# EEZ_AUX_PS_r5B8.net
KiCad netlist of a schematic drawn in EAGLE
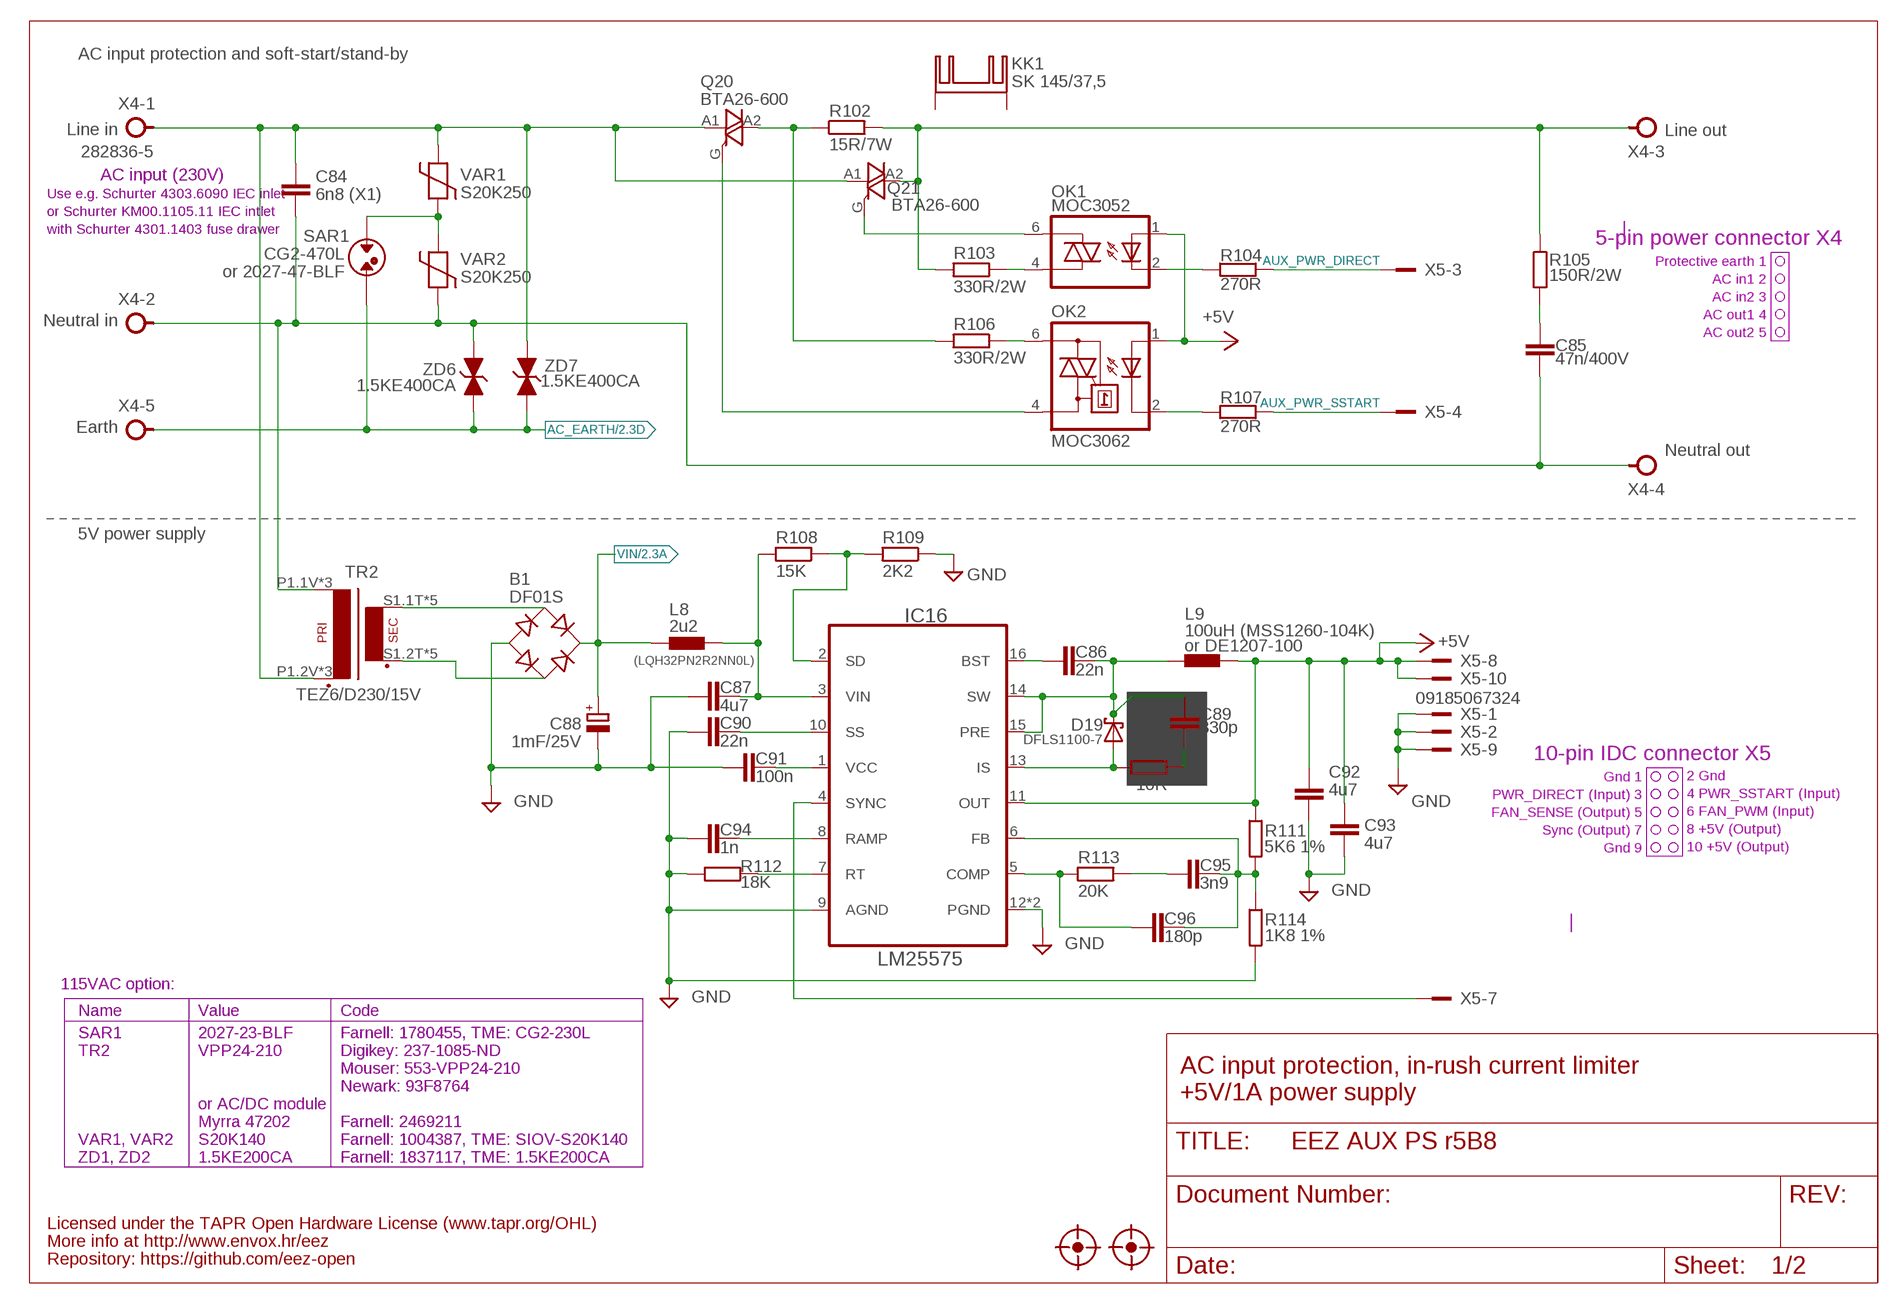
[diagram p0: schematic, sheet 1]
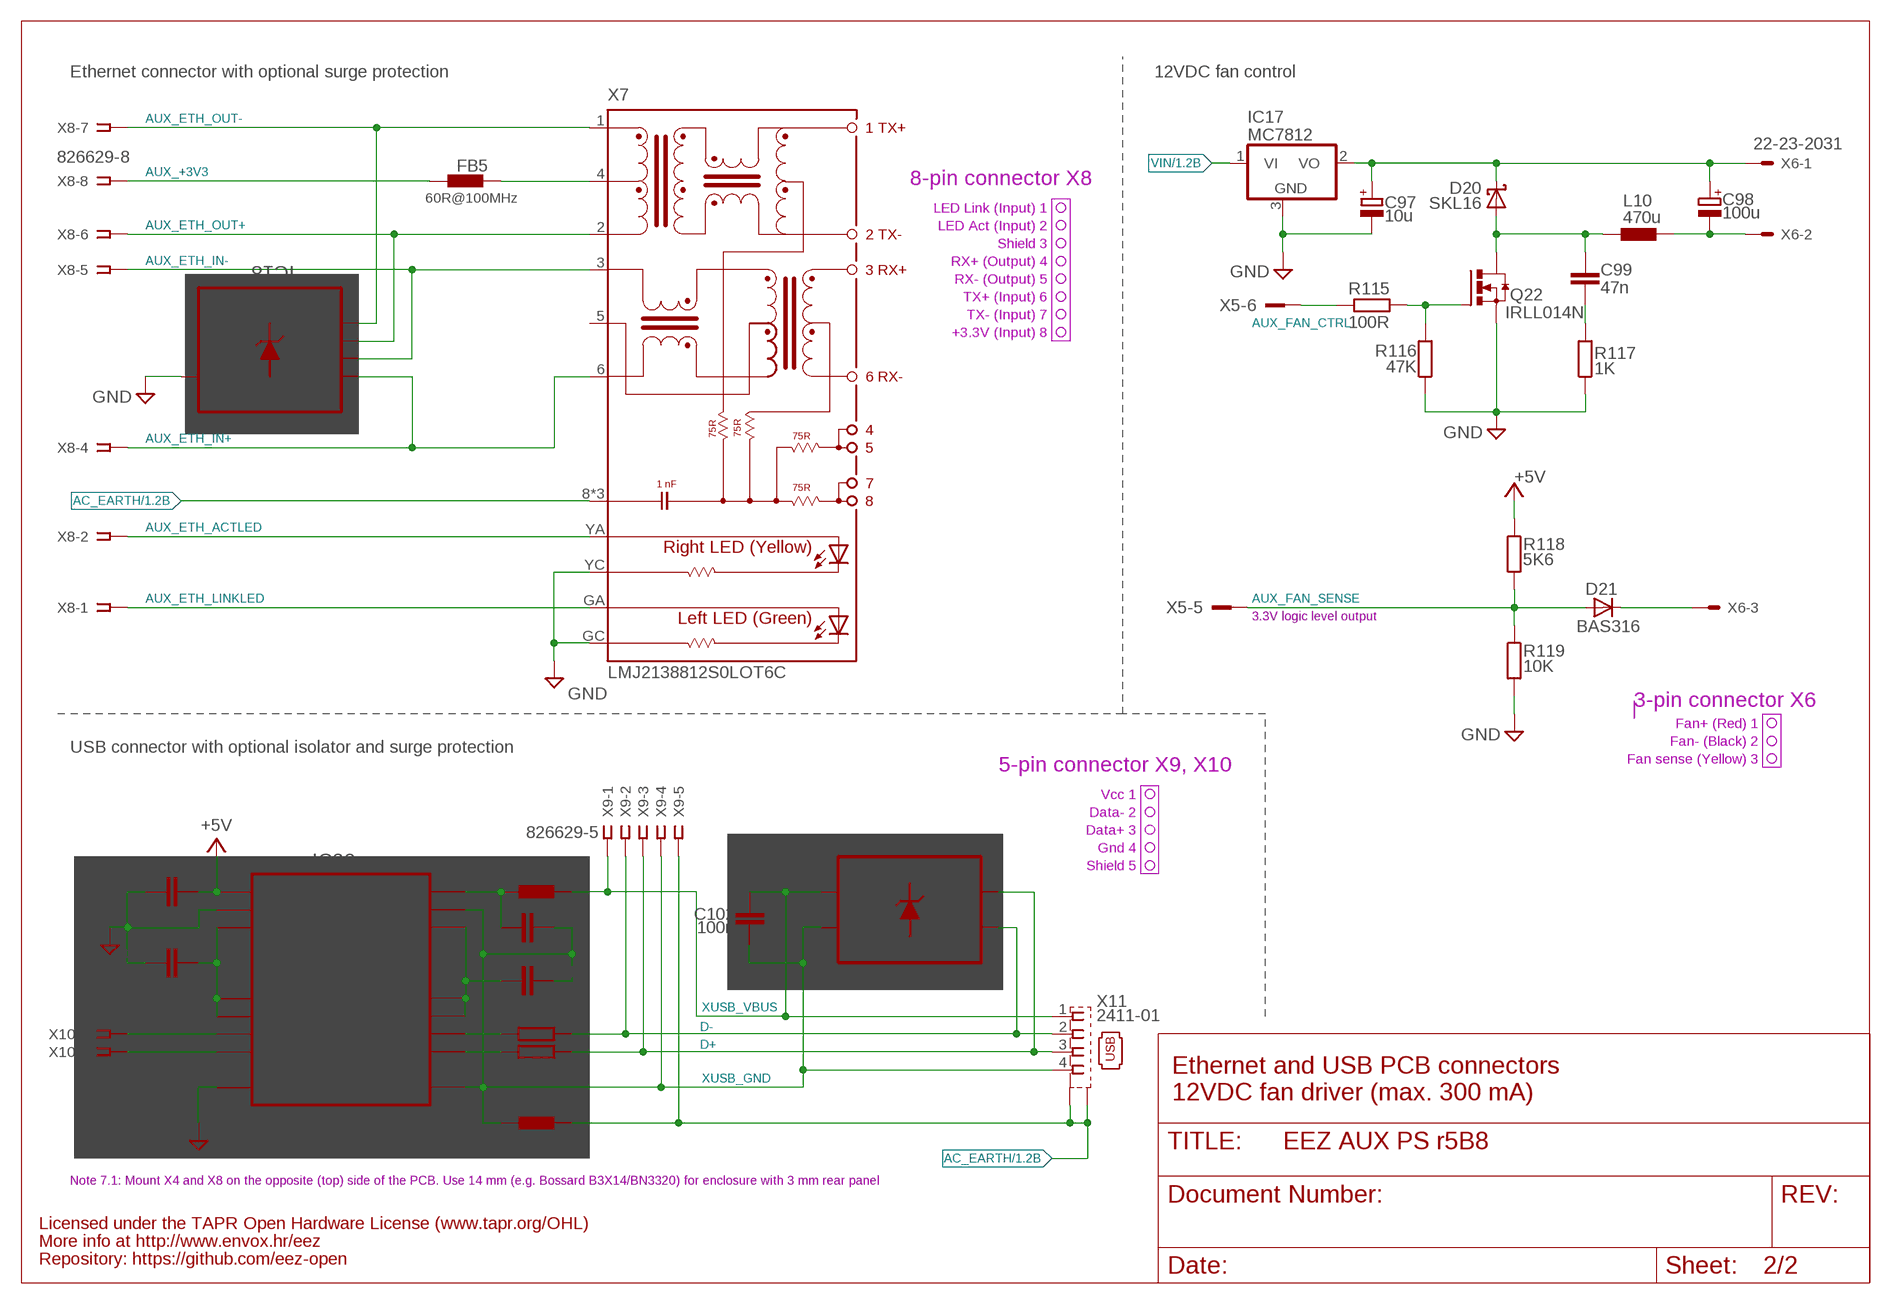
[diagram p1: schematic, sheet 2]

(export (version "E")
  (design (tool "Eeschema 10.0.6"))
  (components
    (comp (ref "B1")
      (value "DF01S")
      (footprint "eagle-import:DFS")
      (libsource (lib "eagle-import") (part "DFS01"))
    )
    (comp (ref "C84")
      (value "6n8 (X1)")
      (footprint "eagle-import:C102-064X133")
      (libsource (lib "eagle-import") (part "C-EU102-064X133"))
    )
    (comp (ref "C85")
      (value "47n/400V")
      (footprint "eagle-import:C075-052X106")
      (libsource (lib "eagle-import") (part "C-EU075-052X106"))
    )
    (comp (ref "C86")
      (value "22n")
      (footprint "eagle-import:C0805")
      (libsource (lib "eagle-import") (part "C-EUC0805"))
    )
    (comp (ref "C87")
      (value "4u7")
      (footprint "eagle-import:C1210")
      (libsource (lib "eagle-import") (part "C-EUC1210"))
    )
    (comp (ref "C88")
      (value "1mF/25V")
      (footprint "eagle-import:ECAP5_10.5")
      (libsource (lib "eagle-import") (part "ECAP5G_10.5MM"))
    )
    (comp (ref "C89")
      (value "330p")
      (footprint "eagle-import:C0805")
      (libsource (lib "eagle-import") (part "C-EUC0805"))
    )
    (comp (ref "C90")
      (value "22n")
      (footprint "eagle-import:C0805")
      (libsource (lib "eagle-import") (part "C-EUC0805"))
    )
    (comp (ref "C91")
      (value "100n")
      (footprint "eagle-import:C0805")
      (libsource (lib "eagle-import") (part "C-EUC0805"))
    )
    (comp (ref "C92")
      (value "4u7")
      (footprint "eagle-import:C1210")
      (libsource (lib "eagle-import") (part "C-EUC1210"))
    )
    (comp (ref "C93")
      (value "4u7")
      (footprint "eagle-import:C1210")
      (libsource (lib "eagle-import") (part "C-EUC1210"))
    )
    (comp (ref "C94")
      (value "1n")
      (footprint "eagle-import:C0805")
      (libsource (lib "eagle-import") (part "C-EUC0805"))
    )
    (comp (ref "C95")
      (value "3n9")
      (footprint "eagle-import:C0805")
      (libsource (lib "eagle-import") (part "C-EUC0805"))
    )
    (comp (ref "C96")
      (value "180p")
      (footprint "eagle-import:C0805")
      (libsource (lib "eagle-import") (part "C-EUC0805"))
    )
    (comp (ref "D19")
      (value "DFLS1100-7")
      (footprint "eagle-import:SOD123")
      (libsource (lib "eagle-import") (part "SCHOTTKYSOD123"))
    )
    (comp (ref "IC16")
      (value "LM25575")
      (footprint "eagle-import:SOP65P640X110-17N")
      (libsource (lib "eagle-import") (part "LM(2)5575"))
    )
    (comp (ref "KK1")
      (value "SK 145/37,5")
      (footprint "eagle-import:SK145")
      (libsource (lib "eagle-import") (part "SK145"))
    )
    (comp (ref "L8")
      (value "2u2")
      (footprint "eagle-import:L1210")
      (libsource (lib "eagle-import") (part "L1210"))
    )
    (comp (ref "L9")
      (value "100uH (MSS1260-104K)")
      (footprint "eagle-import:MSS1278")
      (libsource (lib "eagle-import") (part "COILCRAFT_MSS1278"))
    )
    (comp (ref "OK1")
      (value "MOC3052")
      (footprint "eagle-import:DIL6-SMD")
      (libsource (lib "eagle-import") (part "MOC305X"))
    )
    (comp (ref "OK2")
      (value "MOC3062")
      (footprint "eagle-import:DIL6-SMD")
      (fields
        (field (name "MF") "FAIRCHILD SEMICONDUCTOR")
        (field (name "MPN") "MOC3033S-M")
        (field (name "MF_1") "FAIRCHILD SEMICONDUCTOR")
        (field (name "MPN_1") "MOC3033S-M")
        (field (name "OC_FARNELL") "unknown")
        (field (name "OC_NEWARK") "05C2878")
      )
      (libsource (lib "eagle-import") (part "MOC30S33"))
    )
    (comp (ref "Q20")
      (value "BTA26-600")
      (footprint "eagle-import:TOP3S-1")
      (libsource (lib "eagle-import") (part "BTA26-V"))
    )
    (comp (ref "Q21")
      (value "BTA26-600")
      (footprint "eagle-import:TOP3S-1")
      (libsource (lib "eagle-import") (part "BTA26-V"))
    )
    (comp (ref "R102")
      (value "15R/7W")
      (footprint "eagle-import:R_0913")
      (libsource (lib "eagle-import") (part "R_EU7W"))
    )
    (comp (ref "R103")
      (value "330R/2W")
      (footprint "eagle-import:R2512")
      (libsource (lib "eagle-import") (part "R-EU_R2512"))
    )
    (comp (ref "R104")
      (value "270R")
      (footprint "eagle-import:R0805")
      (libsource (lib "eagle-import") (part "R-EU_R0805"))
    )
    (comp (ref "R105")
      (value "150R/2W")
      (footprint "eagle-import:R2512")
      (libsource (lib "eagle-import") (part "R-EU_R2512"))
    )
    (comp (ref "R106")
      (value "330R/2W")
      (footprint "eagle-import:R2512")
      (libsource (lib "eagle-import") (part "R-EU_R2512"))
    )
    (comp (ref "R107")
      (value "270R")
      (footprint "eagle-import:R0805")
      (libsource (lib "eagle-import") (part "R-EU_R0805"))
    )
    (comp (ref "R108")
      (value "15K")
      (footprint "eagle-import:R0805")
      (libsource (lib "eagle-import") (part "R-EU_R0805"))
    )
    (comp (ref "R109")
      (value "2K2")
      (footprint "eagle-import:R0805")
      (libsource (lib "eagle-import") (part "R-EU_R0805"))
    )
    (comp (ref "R110")
      (value "10R")
      (footprint "eagle-import:R1206")
      (libsource (lib "eagle-import") (part "R-EU_R1206"))
    )
    (comp (ref "R111")
      (value "5K6 1%")
      (footprint "eagle-import:R0805")
      (libsource (lib "eagle-import") (part "R-EU_R0805"))
    )
    (comp (ref "R112")
      (value "18K")
      (footprint "eagle-import:R0805")
      (libsource (lib "eagle-import") (part "R-EU_R0805"))
    )
    (comp (ref "R113")
      (value "20K")
      (footprint "eagle-import:R0805")
      (libsource (lib "eagle-import") (part "R-EU_R0805"))
    )
    (comp (ref "R114")
      (value "1K8 1%")
      (footprint "eagle-import:R0805")
      (libsource (lib "eagle-import") (part "R-EU_R0805"))
    )
    (comp (ref "SAR1")
      (value "CG2-470L")
      (footprint "eagle-import:SAR")
      (libsource (lib "eagle-import") (part "SAR"))
    )
    (comp (ref "TR2")
      (value "TEZ6/D230/15V")
      (footprint "eagle-import:PCB_TRAFO6VA_7.5W")
      (libsource (lib "eagle-import") (part "PCB_TRAFO6VA_TEZ+VPP+MYRRA"))
    )
    (comp (ref "U$13")
      (value "FIDUCIAL_2")
      (footprint "eagle-import:FIDUCIAL_DUAL")
      (libsource (lib "eagle-import") (part "FIDUCIAL_2"))
    )
    (comp (ref "U$14")
      (value "FIDUCIAL_2")
      (footprint "eagle-import:FIDUCIAL_DUAL")
      (libsource (lib "eagle-import") (part "FIDUCIAL_2"))
    )
    (comp (ref "VAR1")
      (value "S20K250")
      (footprint "eagle-import:VARISTOR")
      (libsource (lib "eagle-import") (part "VARISTOR"))
    )
    (comp (ref "VAR2")
      (value "S20K250")
      (footprint "eagle-import:VARISTOR")
      (libsource (lib "eagle-import") (part "VARISTOR"))
    )
    (comp (ref "X4")
      (value "282836-5")
      (footprint "eagle-import:TBLOCK5.0_5")
      (libsource (lib "eagle-import") (part "TBLOCK5.0_5A"))
    )
    (comp (ref "X5")
      (value "09185067324")
      (footprint "eagle-import:IDC-10PIN")
      (fields (field (name "TME") "T821-1-10-S1 "))
      (libsource (lib "eagle-import") (part "IDC-10PINBLACK"))
    )
    (comp (ref "ZD6")
      (value "1.5KE400CA")
      (footprint "eagle-import:DO201-BIDIR")
      (libsource (lib "eagle-import") (part "1.5KE-BIDIR"))
    )
    (comp (ref "ZD7")
      (value "1.5KE400CA")
      (footprint "eagle-import:DO201-BIDIR")
      (libsource (lib "eagle-import") (part "1.5KE-BIDIR"))
    )
    (comp (ref "C97")
      (value "10u")
      (footprint "eagle-import:PANASONIC_C")
      (libsource (lib "eagle-import") (part "MyLib6_ECAPPANASONIC_C"))
    )
    (comp (ref "C98")
      (value "100u")
      (footprint "eagle-import:CAPAE660X610N")
      (libsource (lib "eagle-import") (part "ECAPPANASONIC_H"))
    )
    (comp (ref "C99")
      (value "47n")
      (footprint "eagle-import:C0805")
      (libsource (lib "eagle-import") (part "C-EUC0805"))
    )
    (comp (ref "C100")
      (value "100n")
      (footprint "eagle-import:C0603")
      (libsource (lib "eagle-import") (part "C-EUC0603"))
    )
    (comp (ref "C101")
      (value "100n")
      (footprint "eagle-import:C0603")
      (libsource (lib "eagle-import") (part "C-EUC0603"))
    )
    (comp (ref "C102")
      (value "100n")
      (footprint "eagle-import:C0603")
      (libsource (lib "eagle-import") (part "C-EUC0603"))
    )
    (comp (ref "C103")
      (value "100n")
      (footprint "eagle-import:C0603")
      (libsource (lib "eagle-import") (part "C-EUC0603"))
    )
    (comp (ref "C104")
      (value "100n")
      (footprint "eagle-import:C0603")
      (libsource (lib "eagle-import") (part "C-EUC0603"))
    )
    (comp (ref "D20")
      (value "SKL16")
      (footprint "eagle-import:SOD123")
      (libsource (lib "eagle-import") (part "SCHOTTKYSOD123"))
    )
    (comp (ref "D21")
      (value "BAS316")
      (footprint "eagle-import:SOD323-W")
      (libsource (lib "eagle-import") (part "DIODE-SOD323-W"))
    )
    (comp (ref "FB5")
      (value "60R@100MHz")
      (footprint "eagle-import:BEAD0603")
      (libsource (lib "eagle-import") (part "FERRITE_BEAD0603"))
    )
    (comp (ref "FB6")
      (value "60R@100MHz")
      (footprint "eagle-import:BEAD0603")
      (libsource (lib "eagle-import") (part "FERRITE_BEAD0603"))
    )
    (comp (ref "FB7")
      (value "60R@100MHz")
      (footprint "eagle-import:BEAD0603")
      (libsource (lib "eagle-import") (part "FERRITE_BEAD0603"))
    )
    (comp (ref "IC17")
      (value "MC7812")
      (footprint "eagle-import:TO252")
      (libsource (lib "eagle-import") (part "MC78XX"))
    )
    (comp (ref "IC18")
      (value "TPD4E002DRLR")
      (footprint "eagle-import:SOT50P280X60-5N")
      (libsource (lib "eagle-import") (part "TPD4E002DRLR"))
    )
    (comp (ref "IC19")
      (value "TPD2E001DZDR")
      (footprint "eagle-import:SOP192P292X122-4N")
      (libsource (lib "eagle-import") (part "TPD2E001DZDR"))
    )
    (comp (ref "IC20")
      (value "ADUM3160BRWZ")
      (footprint "eagle-import:SOIC-16W")
      (libsource (lib "eagle-import") (part "ADUM3160BRWZWIDE"))
    )
    (comp (ref "L10")
      (value "470u")
      (footprint "eagle-import:DE0704")
      (libsource (lib "eagle-import") (part "DE0704"))
    )
    (comp (ref "Q22")
      (value "IRLL014N")
      (footprint "eagle-import:SOT223")
      (libsource (lib "eagle-import") (part "N-HEXFET-2D_?-SOT232IRLL014N"))
    )
    (comp (ref "R115")
      (value "100R")
      (footprint "eagle-import:R0805")
      (libsource (lib "eagle-import") (part "R-EU_R0805"))
    )
    (comp (ref "R116")
      (value "47K")
      (footprint "eagle-import:R0805")
      (libsource (lib "eagle-import") (part "R-EU_R0805"))
    )
    (comp (ref "R117")
      (value "1K")
      (footprint "eagle-import:R0805")
      (libsource (lib "eagle-import") (part "R-EU_R0805"))
    )
    (comp (ref "R118")
      (value "5K6")
      (footprint "eagle-import:R0805")
      (libsource (lib "eagle-import") (part "R-EU_R0805"))
    )
    (comp (ref "R119")
      (value "10K")
      (footprint "eagle-import:R0805")
      (libsource (lib "eagle-import") (part "R-EU_R0805"))
    )
    (comp (ref "R120")
      (value "22R")
      (footprint "eagle-import:R0805")
      (libsource (lib "eagle-import") (part "R-EU_R0805"))
    )
    (comp (ref "R121")
      (value "22R")
      (footprint "eagle-import:R0805")
      (libsource (lib "eagle-import") (part "R-EU_R0805"))
    )
    (comp (ref "X6")
      (value "22-23-2031")
      (footprint "eagle-import:22-23-2031")
      (fields (field (name "MF") "MOLEX"))
      (libsource (lib "eagle-import") (part "22-23-2031"))
    )
    (comp (ref "X7")
      (value "LMJ2138812S0LOT6C")
      (footprint "eagle-import:RJ45-VERT")
      (libsource (lib "eagle-import") (part "RJ45-VERT"))
    )
    (comp (ref "X8")
      (value "826629-8")
      (footprint "eagle-import:SSW-108-02-S-S")
      (fields (field (name "MPN") "SSW-108-02-S-S"))
      (libsource (lib "eagle-import") (part "SSW-108-02-S-S"))
    )
    (comp (ref "X9")
      (value "826629-5")
      (footprint "eagle-import:SSW-105-02-S-S")
      (fields (field (name "MPN") "SSW-105-02-S-S"))
      (libsource (lib "eagle-import") (part "SSW-105-02-S-S"))
    )
    (comp (ref "X10")
      (value "826629-5")
      (footprint "eagle-import:SSW-105-02-S-S")
      (fields (field (name "MPN") "SSW-105-02-S-S"))
      (libsource (lib "eagle-import") (part "SSW-105-02-S-S"))
    )
    (comp (ref "X11")
      (value "2411-01")
      (footprint "eagle-import:KUSBVX-BS1N")
      (libsource (lib "eagle-import") (part "KUSBVX-BS1N"))
    )
  )
  (nets
    (net (code "1") (name "+5V") (class "Default")
      (node (ref "C100") (pin "1") (pinfunction "1_1") (pintype "passive"))
      (node (ref "C92") (pin "1") (pinfunction "1_1") (pintype "passive"))
      (node (ref "C93") (pin "1") (pinfunction "1_1") (pintype "passive"))
      (node (ref "IC16") (pin "11") (pinfunction "OUT_11") (pintype "output"))
      (node (ref "IC20") (pin "16") (pinfunction "VBUS2_16") (pintype "power_in"))
      (node (ref "L9") (pin "2") (pinfunction "2_2") (pintype "passive"))
      (node (ref "OK1") (pin "1") (pinfunction "A_1") (pintype "passive"))
      (node (ref "OK2") (pin "1") (pinfunction "A_1") (pintype "passive"))
      (node (ref "R111") (pin "1") (pinfunction "1_1") (pintype "passive"))
      (node (ref "R118") (pin "1") (pinfunction "1_1") (pintype "passive"))
      (node (ref "X5") (pin "10") (pinfunction "1_10") (pintype "passive"))
      (node (ref "X5") (pin "8") (pinfunction "1_8") (pintype "passive"))
    )
    (net (code "2") (name "AC_EARTH") (class "Default")
      (node (ref "FB7") (pin "P$1") (pinfunction "1_P$1") (pintype "passive"))
      (node (ref "SAR1") (pin "P$2") (pinfunction "P$2_P$2") (pintype "bidirectional"))
      (node (ref "X11") (pin "M1") (pinfunction "S1_M1") (pintype "passive"))
      (node (ref "X11") (pin "M2") (pinfunction "S2_M2") (pintype "passive"))
      (node (ref "X4") (pin "5") (pinfunction "1_5") (pintype "bidirectional"))
      (node (ref "X7") (pin "8") (pinfunction "SH_8") (pintype "input"))
      (node (ref "X7") (pin "SH1") (pinfunction "SH_SH1") (pintype "input"))
      (node (ref "X7") (pin "SH2") (pinfunction "SH_SH2") (pintype "input"))
      (node (ref "X9") (pin "5") (pinfunction "1_5") (pintype "passive"))
      (node (ref "ZD6") (pin "C") (pinfunction "1_C") (pintype "passive"))
      (node (ref "ZD7") (pin "C") (pinfunction "1_C") (pintype "passive"))
    )
    (net (code "3") (name "AUX_+3V3") (class "Default")
      (node (ref "FB5") (pin "P$2") (pinfunction "2_P$2") (pintype "passive"))
      (node (ref "X8") (pin "8") (pinfunction "1_8") (pintype "passive"))
    )
    (net (code "4") (name "AUX_ETH_ACTLED") (class "Default")
      (node (ref "X7") (pin "YA") (pinfunction "YELLOW_A_YA") (pintype "passive"))
      (node (ref "X8") (pin "2") (pinfunction "1_2") (pintype "passive"))
    )
    (net (code "5") (name "AUX_ETH_IN+") (class "Default")
      (node (ref "IC18") (pin "5") (pinfunction "IO4_5") (pintype "bidirectional"))
      (node (ref "X7") (pin "6") (pinfunction "RD-_6") (pintype "input"))
      (node (ref "X8") (pin "4") (pinfunction "1_4") (pintype "passive"))
    )
    (net (code "6") (name "AUX_ETH_IN-") (class "Default")
      (node (ref "IC18") (pin "4") (pinfunction "IO3_4") (pintype "bidirectional"))
      (node (ref "X7") (pin "3") (pinfunction "RD+_3") (pintype "input"))
      (node (ref "X8") (pin "5") (pinfunction "1_5") (pintype "passive"))
    )
    (net (code "7") (name "AUX_ETH_LINKLED") (class "Default")
      (node (ref "X7") (pin "GA") (pinfunction "GREEN-A_GA") (pintype "passive"))
      (node (ref "X8") (pin "1") (pinfunction "1_1") (pintype "passive"))
    )
    (net (code "8") (name "AUX_ETH_OUT+") (class "Default")
      (node (ref "IC18") (pin "3") (pinfunction "IO2_3") (pintype "bidirectional"))
      (node (ref "X7") (pin "2") (pinfunction "TD-_2") (pintype "input"))
      (node (ref "X8") (pin "6") (pinfunction "1_6") (pintype "passive"))
    )
    (net (code "9") (name "AUX_ETH_OUT-") (class "Default")
      (node (ref "IC18") (pin "1") (pinfunction "IO1_1") (pintype "bidirectional"))
      (node (ref "X7") (pin "1") (pinfunction "TD+_1") (pintype "input"))
      (node (ref "X8") (pin "7") (pinfunction "1_7") (pintype "passive"))
    )
    (net (code "10") (name "AUX_FAN_CTRL") (class "Default")
      (node (ref "R115") (pin "2") (pinfunction "2_2") (pintype "passive"))
      (node (ref "X5") (pin "6") (pinfunction "1_6") (pintype "passive"))
    )
    (net (code "11") (name "AUX_FAN_SENSE") (class "Default")
      (node (ref "D21") (pin "A") (pinfunction "A_A") (pintype "passive"))
      (node (ref "R118") (pin "2") (pinfunction "2_2") (pintype "passive"))
      (node (ref "R119") (pin "1") (pinfunction "1_1") (pintype "passive"))
      (node (ref "X5") (pin "5") (pinfunction "1_5") (pintype "passive"))
    )
    (net (code "12") (name "AUX_PWR_DIRECT") (class "Default")
      (node (ref "R104") (pin "2") (pinfunction "2_2") (pintype "passive"))
      (node (ref "X5") (pin "3") (pinfunction "1_3") (pintype "passive"))
    )
    (net (code "13") (name "AUX_PWR_SSTART") (class "Default")
      (node (ref "R107") (pin "2") (pinfunction "2_2") (pintype "passive"))
      (node (ref "X5") (pin "4") (pinfunction "1_4") (pintype "passive"))
    )
    (net (code "14") (name "D+") (class "Default")
      (node (ref "IC19") (pin "2") (pinfunction "IO1_2") (pintype "bidirectional"))
      (node (ref "R121") (pin "1") (pinfunction "1_1") (pintype "passive"))
      (node (ref "X11") (pin "3") (pinfunction "3_3") (pintype "passive"))
      (node (ref "X9") (pin "3") (pinfunction "1_3") (pintype "passive"))
    )
    (net (code "15") (name "D-") (class "Default")
      (node (ref "IC19") (pin "3") (pinfunction "IO2_3") (pintype "bidirectional"))
      (node (ref "R120") (pin "1") (pinfunction "1_1") (pintype "passive"))
      (node (ref "X11") (pin "2") (pinfunction "2_2") (pintype "passive"))
      (node (ref "X9") (pin "2") (pinfunction "1_2") (pintype "passive"))
    )
    (net (code "16") (name "GND") (class "Default")
      (node (ref "B1") (pin "-") (pinfunction "-_-") (pintype "passive"))
      (node (ref "C100") (pin "2") (pinfunction "2_2") (pintype "passive"))
      (node (ref "C103") (pin "2") (pinfunction "2_2") (pintype "passive"))
      (node (ref "C87") (pin "2") (pinfunction "2_2") (pintype "passive"))
      (node (ref "C88") (pin "-") (pinfunction "-_-") (pintype "passive"))
      (node (ref "C90") (pin "2") (pinfunction "2_2") (pintype "passive"))
      (node (ref "C91") (pin "1") (pinfunction "1_1") (pintype "passive"))
      (node (ref "C92") (pin "2") (pinfunction "2_2") (pintype "passive"))
      (node (ref "C93") (pin "2") (pinfunction "2_2") (pintype "passive"))
      (node (ref "C94") (pin "1") (pinfunction "1_1") (pintype "passive"))
      (node (ref "C97") (pin "2") (pinfunction "-_2") (pintype "passive"))
      (node (ref "IC16") (pin "12") (pinfunction "PGND_12") (pintype "passive"))
      (node (ref "IC16") (pin "9") (pinfunction "AGND_9") (pintype "passive"))
      (node (ref "IC16") (pin "TP") (pinfunction "PGND_TP") (pintype "passive"))
      (node (ref "IC17") (pin "3") (pinfunction "GND_3") (pintype "passive"))
      (node (ref "IC18") (pin "2") (pinfunction "GND_2") (pintype "passive"))
      (node (ref "IC20") (pin "15") (pinfunction "GND2_2_15") (pintype "passive"))
      (node (ref "IC20") (pin "9") (pinfunction "GND2_9") (pintype "passive"))
      (node (ref "Q22") (pin "3") (pinfunction "S_3") (pintype "passive"))
      (node (ref "R109") (pin "1") (pinfunction "1_1") (pintype "passive"))
      (node (ref "R112") (pin "2") (pinfunction "2_2") (pintype "passive"))
      (node (ref "R114") (pin "2") (pinfunction "2_2") (pintype "passive"))
      (node (ref "R116") (pin "1") (pinfunction "1_1") (pintype "passive"))
      (node (ref "R117") (pin "1") (pinfunction "1_1") (pintype "passive"))
      (node (ref "R119") (pin "2") (pinfunction "2_2") (pintype "passive"))
      (node (ref "X5") (pin "1") (pinfunction "1_1") (pintype "passive"))
      (node (ref "X5") (pin "2") (pinfunction "1_2") (pintype "passive"))
      (node (ref "X5") (pin "9") (pinfunction "1_9") (pintype "passive"))
      (node (ref "X7") (pin "GC") (pinfunction "GREEN-C_GC") (pintype "passive"))
      (node (ref "X7") (pin "YC") (pinfunction "YELLOW-C_YC") (pintype "passive"))
    )
    (net (code "17") (name "Net-(B1-PadAC1)") (class "Default")
      (node (ref "B1") (pin "AC1") (pinfunction "AC1_AC1") (pintype "passive"))
      (node (ref "TR2") (pin "S1.1T") (pinfunction "S1_S1.1T") (pintype "passive"))
      (node (ref "TR2") (pin "S1.1V") (pinfunction "S1_S1.1V") (pintype "passive"))
      (node (ref "TR2") (pin "S2.1T") (pinfunction "S1_S2.1T") (pintype "passive"))
      (node (ref "TR2") (pin "S2.1V") (pinfunction "S1_S2.1V") (pintype "passive"))
      (node (ref "TR2") (pin "S2M") (pinfunction "S1_S2M") (pintype "passive"))
    )
    (net (code "18") (name "Net-(B1-PadAC2)") (class "Default")
      (node (ref "B1") (pin "AC2") (pinfunction "AC2_AC2") (pintype "passive"))
      (node (ref "TR2") (pin "S1.2T") (pinfunction "S2_S1.2T") (pintype "passive"))
      (node (ref "TR2") (pin "S1.2V") (pinfunction "S2_S1.2V") (pintype "passive"))
      (node (ref "TR2") (pin "S1M") (pinfunction "S2_S1M") (pintype "passive"))
      (node (ref "TR2") (pin "S2.2T") (pinfunction "S2_S2.2T") (pintype "passive"))
      (node (ref "TR2") (pin "S2.2V") (pinfunction "S2_S2.2V") (pintype "passive"))
    )
    (net (code "19") (name "Net-(C85-Pad2)") (class "Default")
      (node (ref "C85") (pin "2") (pinfunction "2_2") (pintype "passive"))
      (node (ref "R105") (pin "2") (pinfunction "2_2") (pintype "passive"))
    )
    (net (code "20") (name "Net-(C89-Pad2)") (class "Default")
      (node (ref "C89") (pin "2") (pinfunction "2_2") (pintype "passive"))
      (node (ref "R110") (pin "2") (pinfunction "2_2") (pintype "passive"))
    )
    (net (code "21") (name "Net-(C95-Pad2)") (class "Default")
      (node (ref "C95") (pin "2") (pinfunction "2_2") (pintype "passive"))
      (node (ref "R113") (pin "2") (pinfunction "2_2") (pintype "passive"))
    )
    (net (code "22") (name "Net-(C97-+)") (class "Default")
      (node (ref "C97") (pin "1") (pinfunction "+_1") (pintype "passive"))
      (node (ref "C98") (pin "1") (pinfunction "+_1") (pintype "passive"))
      (node (ref "D20") (pin "C") (pinfunction "C_C") (pintype "passive"))
      (node (ref "IC17") (pin "2") (pinfunction "VO_2") (pintype "passive"))
      (node (ref "X6") (pin "1") (pinfunction "S_1") (pintype "passive"))
    )
    (net (code "23") (name "Net-(C98--)") (class "Default")
      (node (ref "C98") (pin "2") (pinfunction "-_2") (pintype "passive"))
      (node (ref "L10") (pin "1") (pinfunction "1_1") (pintype "passive"))
      (node (ref "X6") (pin "2") (pinfunction "S_2") (pintype "passive"))
    )
    (net (code "24") (name "Net-(C99-Pad1)") (class "Default")
      (node (ref "C99") (pin "1") (pinfunction "1_1") (pintype "passive"))
      (node (ref "R117") (pin "2") (pinfunction "2_2") (pintype "passive"))
    )
    (net (code "25") (name "Net-(C99-Pad2)") (class "Default")
      (node (ref "C99") (pin "2") (pinfunction "2_2") (pintype "passive"))
      (node (ref "D20") (pin "A") (pinfunction "A_A") (pintype "passive"))
      (node (ref "L10") (pin "2") (pinfunction "2_2") (pintype "passive"))
      (node (ref "Q22") (pin "2") (pinfunction "D_2") (pintype "passive"))
      (node (ref "Q22") (pin "4") (pinfunction "D_4") (pintype "passive"))
    )
    (net (code "26") (name "Net-(FB5-1)") (class "Default")
      (node (ref "FB5") (pin "P$1") (pinfunction "1_P$1") (pintype "passive"))
      (node (ref "X7") (pin "4") (pinfunction "CT_4") (pintype "input"))
    )
    (net (code "27") (name "Net-(FB6-2)") (class "Default")
      (node (ref "C101") (pin "1") (pinfunction "1_1") (pintype "passive"))
      (node (ref "FB6") (pin "P$2") (pinfunction "2_P$2") (pintype "passive"))
      (node (ref "IC20") (pin "1") (pinfunction "VBUS1_1") (pintype "power_in"))
    )
    (net (code "28") (name "Net-(IC16-BST)") (class "Default")
      (node (ref "C86") (pin "2") (pinfunction "2_2") (pintype "passive"))
      (node (ref "IC16") (pin "16") (pinfunction "BST_16") (pintype "input"))
    )
    (net (code "29") (name "Net-(IC16-COMP)") (class "Default")
      (node (ref "C96") (pin "2") (pinfunction "2_2") (pintype "passive"))
      (node (ref "IC16") (pin "5") (pinfunction "COMP_5") (pintype "input"))
      (node (ref "R113") (pin "1") (pinfunction "1_1") (pintype "passive"))
    )
    (net (code "30") (name "Net-(IC16-FB)") (class "Default")
      (node (ref "C95") (pin "1") (pinfunction "1_1") (pintype "passive"))
      (node (ref "C96") (pin "1") (pinfunction "1_1") (pintype "passive"))
      (node (ref "IC16") (pin "6") (pinfunction "FB_6") (pintype "input"))
      (node (ref "R111") (pin "2") (pinfunction "2_2") (pintype "passive"))
      (node (ref "R114") (pin "1") (pinfunction "1_1") (pintype "passive"))
    )
    (net (code "31") (name "Net-(IC16-IS)") (class "Default")
      (node (ref "D19") (pin "A") (pinfunction "A_A") (pintype "passive"))
      (node (ref "IC16") (pin "13") (pinfunction "IS_13") (pintype "input"))
      (node (ref "R110") (pin "1") (pinfunction "1_1") (pintype "passive"))
    )
    (net (code "32") (name "Net-(IC16-PRE)") (class "Default")
      (node (ref "C86") (pin "1") (pinfunction "1_1") (pintype "passive"))
      (node (ref "C89") (pin "1") (pinfunction "1_1") (pintype "passive"))
      (node (ref "D19") (pin "C") (pinfunction "C_C") (pintype "passive"))
      (node (ref "IC16") (pin "14") (pinfunction "SW_14") (pintype "output"))
      (node (ref "IC16") (pin "15") (pinfunction "PRE_15") (pintype "input"))
      (node (ref "L9") (pin "1") (pinfunction "1_1") (pintype "passive"))
    )
    (net (code "33") (name "Net-(IC16-RAMP)") (class "Default")
      (node (ref "C94") (pin "2") (pinfunction "2_2") (pintype "passive"))
      (node (ref "IC16") (pin "8") (pinfunction "RAMP_8") (pintype "input"))
    )
    (net (code "34") (name "Net-(IC16-RT)") (class "Default")
      (node (ref "IC16") (pin "7") (pinfunction "RT_7") (pintype "input"))
      (node (ref "R112") (pin "1") (pinfunction "1_1") (pintype "passive"))
    )
    (net (code "35") (name "Net-(IC16-SD)") (class "Default")
      (node (ref "IC16") (pin "2") (pinfunction "SD_2") (pintype "input"))
      (node (ref "R108") (pin "1") (pinfunction "1_1") (pintype "passive"))
      (node (ref "R109") (pin "2") (pinfunction "2_2") (pintype "passive"))
    )
    (net (code "36") (name "Net-(IC16-SS)") (class "Default")
      (node (ref "C90") (pin "1") (pinfunction "1_1") (pintype "passive"))
      (node (ref "IC16") (pin "10") (pinfunction "SS_10") (pintype "input"))
    )
    (net (code "37") (name "Net-(IC16-SYNC)") (class "Default")
      (node (ref "IC16") (pin "4") (pinfunction "SYNC_4") (pintype "input"))
      (node (ref "X5") (pin "7") (pinfunction "1_7") (pintype "passive"))
    )
    (net (code "38") (name "Net-(IC16-VCC)") (class "Default")
      (node (ref "C91") (pin "2") (pinfunction "2_2") (pintype "passive"))
      (node (ref "IC16") (pin "1") (pinfunction "VCC_1") (pintype "power_in"))
    )
    (net (code "39") (name "Net-(IC16-VIN)") (class "Default")
      (node (ref "C87") (pin "1") (pinfunction "1_1") (pintype "passive"))
      (node (ref "IC16") (pin "3") (pinfunction "VIN_3") (pintype "input"))
      (node (ref "L8") (pin "2") (pinfunction "2_2") (pintype "passive"))
      (node (ref "R108") (pin "2") (pinfunction "2_2") (pintype "passive"))
    )
    (net (code "40") (name "Net-(IC20-DD+)") (class "Default")
      (node (ref "IC20") (pin "10") (pinfunction "DD+_10") (pintype "bidirectional"))
      (node (ref "X10") (pin "3") (pinfunction "1_3") (pintype "passive"))
    )
    (net (code "41") (name "Net-(IC20-DD-)") (class "Default")
      (node (ref "IC20") (pin "11") (pinfunction "DD-_11") (pintype "bidirectional"))
      (node (ref "X10") (pin "2") (pinfunction "1_2") (pintype "passive"))
    )
    (net (code "42") (name "Net-(IC20-PDEN)") (class "Default")
      (node (ref "C104") (pin "1") (pinfunction "1_1") (pintype "passive"))
      (node (ref "IC20") (pin "3") (pinfunction "VDD1_3") (pintype "power_in"))
      (node (ref "IC20") (pin "4") (pinfunction "PDEN_4") (pintype "input"))
      (node (ref "IC20") (pin "5") (pinfunction "SPU_5") (pintype "input"))
    )
    (net (code "43") (name "Net-(IC20-PIN)") (class "Default")
      (node (ref "C103") (pin "1") (pinfunction "1_1") (pintype "passive"))
      (node (ref "IC20") (pin "12") (pinfunction "PIN_12") (pintype "input"))
      (node (ref "IC20") (pin "13") (pinfunction "SPD_13") (pintype "input"))
      (node (ref "IC20") (pin "14") (pinfunction "VDD2_14") (pintype "power_in"))
    )
    (net (code "44") (name "Net-(IC20-UD+)") (class "Default")
      (node (ref "IC20") (pin "7") (pinfunction "UD+_7") (pintype "bidirectional"))
      (node (ref "R121") (pin "2") (pinfunction "2_2") (pintype "passive"))
    )
    (net (code "45") (name "Net-(IC20-UD-)") (class "Default")
      (node (ref "IC20") (pin "6") (pinfunction "UD-_6") (pintype "bidirectional"))
      (node (ref "R120") (pin "2") (pinfunction "2_2") (pintype "passive"))
    )
    (net (code "46") (name "Net-(OK1-A1)") (class "Default")
      (node (ref "OK1") (pin "4") (pinfunction "A1_4") (pintype "passive"))
      (node (ref "R103") (pin "1") (pinfunction "1_1") (pintype "passive"))
    )
    (net (code "47") (name "Net-(OK1-A2)") (class "Default")
      (node (ref "OK1") (pin "6") (pinfunction "A2_6") (pintype "passive"))
      (node (ref "Q21") (pin "G") (pinfunction "G_G") (pintype "passive"))
    )
    (net (code "48") (name "Net-(OK1-C)") (class "Default")
      (node (ref "OK1") (pin "2") (pinfunction "C_2") (pintype "passive"))
      (node (ref "R104") (pin "1") (pinfunction "1_1") (pintype "passive"))
    )
    (net (code "49") (name "Net-(OK2-A1)") (class "Default")
      (node (ref "OK2") (pin "4") (pinfunction "A1_4") (pintype "passive"))
      (node (ref "Q20") (pin "G") (pinfunction "G_G") (pintype "passive"))
    )
    (net (code "50") (name "Net-(OK2-A2)") (class "Default")
      (node (ref "OK2") (pin "6") (pinfunction "A2_6") (pintype "passive"))
      (node (ref "R106") (pin "1") (pinfunction "1_1") (pintype "passive"))
    )
    (net (code "51") (name "Net-(OK2-C)") (class "Default")
      (node (ref "OK2") (pin "2") (pinfunction "C_2") (pintype "passive"))
      (node (ref "R107") (pin "1") (pinfunction "1_1") (pintype "passive"))
    )
    (net (code "52") (name "Net-(Q20-PadA2)") (class "Default")
      (node (ref "Q20") (pin "A2") (pinfunction "A2_A2") (pintype "passive"))
      (node (ref "R102") (pin "1") (pinfunction "1_1") (pintype "passive"))
      (node (ref "R106") (pin "2") (pinfunction "2_2") (pintype "passive"))
    )
    (net (code "53") (name "Net-(Q22-G)") (class "Default")
      (node (ref "Q22") (pin "1") (pinfunction "G_1") (pintype "passive"))
      (node (ref "R115") (pin "1") (pinfunction "1_1") (pintype "passive"))
      (node (ref "R116") (pin "2") (pinfunction "2_2") (pintype "passive"))
    )
    (net (code "54") (name "Net-(SAR1-PadP$1)") (class "Default")
      (node (ref "SAR1") (pin "P$1") (pinfunction "P$1_P$1") (pintype "bidirectional"))
      (node (ref "VAR1") (pin "P$1") (pinfunction "P$1_P$1") (pintype "bidirectional"))
      (node (ref "VAR2") (pin "P$2") (pinfunction "P$2_P$2") (pintype "bidirectional"))
    )
    (net (code "55") (name "Net-(X4B-1)") (class "Default")
      (node (ref "C84") (pin "2") (pinfunction "2_2") (pintype "passive"))
      (node (ref "C85") (pin "1") (pinfunction "1_1") (pintype "passive"))
      (node (ref "TR2") (pin "P1.1V") (pinfunction "P1_P1.1V") (pintype "passive"))
      (node (ref "TR2") (pin "P1_TEZ") (pinfunction "P1_P1_TEZ") (pintype "passive"))
      (node (ref "TR2") (pin "P2.1V") (pinfunction "P1_P2.1V") (pintype "passive"))
      (node (ref "VAR2") (pin "P$1") (pinfunction "P$1_P$1") (pintype "bidirectional"))
      (node (ref "X4") (pin "2") (pinfunction "1_2") (pintype "bidirectional"))
      (node (ref "X4") (pin "4") (pinfunction "1_4") (pintype "bidirectional"))
      (node (ref "ZD6") (pin "A") (pinfunction "2_A") (pintype "passive"))
    )
    (net (code "56") (name "Net-(X4C-1)") (class "Default")
      (node (ref "Q21") (pin "A2") (pinfunction "A2_A2") (pintype "passive"))
      (node (ref "R102") (pin "2") (pinfunction "2_2") (pintype "passive"))
      (node (ref "R103") (pin "2") (pinfunction "2_2") (pintype "passive"))
      (node (ref "R105") (pin "1") (pinfunction "1_1") (pintype "passive"))
      (node (ref "X4") (pin "3") (pinfunction "1_3") (pintype "bidirectional"))
    )
    (net (code "57") (name "Net-(X6C-S)") (class "Default")
      (node (ref "D21") (pin "C") (pinfunction "C_C") (pintype "passive"))
      (node (ref "X6") (pin "3") (pinfunction "S_3") (pintype "passive"))
    )
    (net (code "58") (name "Net-(ZD7-2)") (class "Default")
      (node (ref "C84") (pin "1") (pinfunction "1_1") (pintype "passive"))
      (node (ref "Q20") (pin "A1") (pinfunction "A1_A1") (pintype "passive"))
      (node (ref "Q21") (pin "A1") (pinfunction "A1_A1") (pintype "passive"))
      (node (ref "TR2") (pin "P1.2V") (pinfunction "P2_P1.2V") (pintype "passive"))
      (node (ref "TR2") (pin "P2.2V") (pinfunction "P2_P2.2V") (pintype "passive"))
      (node (ref "TR2") (pin "P2_TEZ") (pinfunction "P2_P2_TEZ") (pintype "passive"))
      (node (ref "VAR1") (pin "P$2") (pinfunction "P$2_P$2") (pintype "bidirectional"))
      (node (ref "X4") (pin "1") (pinfunction "1_1") (pintype "bidirectional"))
      (node (ref "ZD7") (pin "A") (pinfunction "2_A") (pintype "passive"))
    )
    (net (code "59") (name "VIN") (class "Default")
      (node (ref "B1") (pin "+") (pinfunction "+_+") (pintype "passive"))
      (node (ref "C88") (pin "+") (pinfunction "+_+") (pintype "passive"))
      (node (ref "IC17") (pin "1") (pinfunction "VI_1") (pintype "input"))
      (node (ref "L8") (pin "1") (pinfunction "1_1") (pintype "passive"))
    )
    (net (code "60") (name "XUSB_GND") (class "Default")
      (node (ref "C101") (pin "2") (pinfunction "2_2") (pintype "passive"))
      (node (ref "C102") (pin "1") (pinfunction "1_1") (pintype "passive"))
      (node (ref "C104") (pin "2") (pinfunction "2_2") (pintype "passive"))
      (node (ref "FB7") (pin "P$2") (pinfunction "2_P$2") (pintype "passive"))
      (node (ref "IC19") (pin "1") (pinfunction "GND_1") (pintype "passive"))
      (node (ref "IC20") (pin "2") (pinfunction "GND1_2_2") (pintype "passive"))
      (node (ref "IC20") (pin "8") (pinfunction "GND1_8") (pintype "passive"))
      (node (ref "X11") (pin "4") (pinfunction "4_4") (pintype "passive"))
      (node (ref "X9") (pin "4") (pinfunction "1_4") (pintype "passive"))
    )
    (net (code "61") (name "XUSB_VBUS") (class "Default")
      (node (ref "C102") (pin "2") (pinfunction "2_2") (pintype "passive"))
      (node (ref "FB6") (pin "P$1") (pinfunction "1_P$1") (pintype "passive"))
      (node (ref "IC19") (pin "4") (pinfunction "VCC_4") (pintype "power_in"))
      (node (ref "X11") (pin "1") (pinfunction "1_1") (pintype "passive"))
      (node (ref "X9") (pin "1") (pinfunction "1_1") (pintype "passive"))
    )
    (net (code "62") (name "unconnected-(KK1-K-Pad1)") (class "Default")
      (node (ref "KK1") (pin "1") (pinfunction "K_1") (pintype "passive"))
    )
    (net (code "63") (name "unconnected-(KK1-K-Pad2)") (class "Default")
      (node (ref "KK1") (pin "2") (pinfunction "K_2") (pintype "passive"))
    )
    (net (code "64") (name "unconnected-(X7-CR-Pad5)") (class "Default")
      (node (ref "X7") (pin "5") (pinfunction "CR_5") (pintype "input"))
    )
  )
)
